# rectifiers.net
KiCad netlist of a schematic drawn in Altium Designer
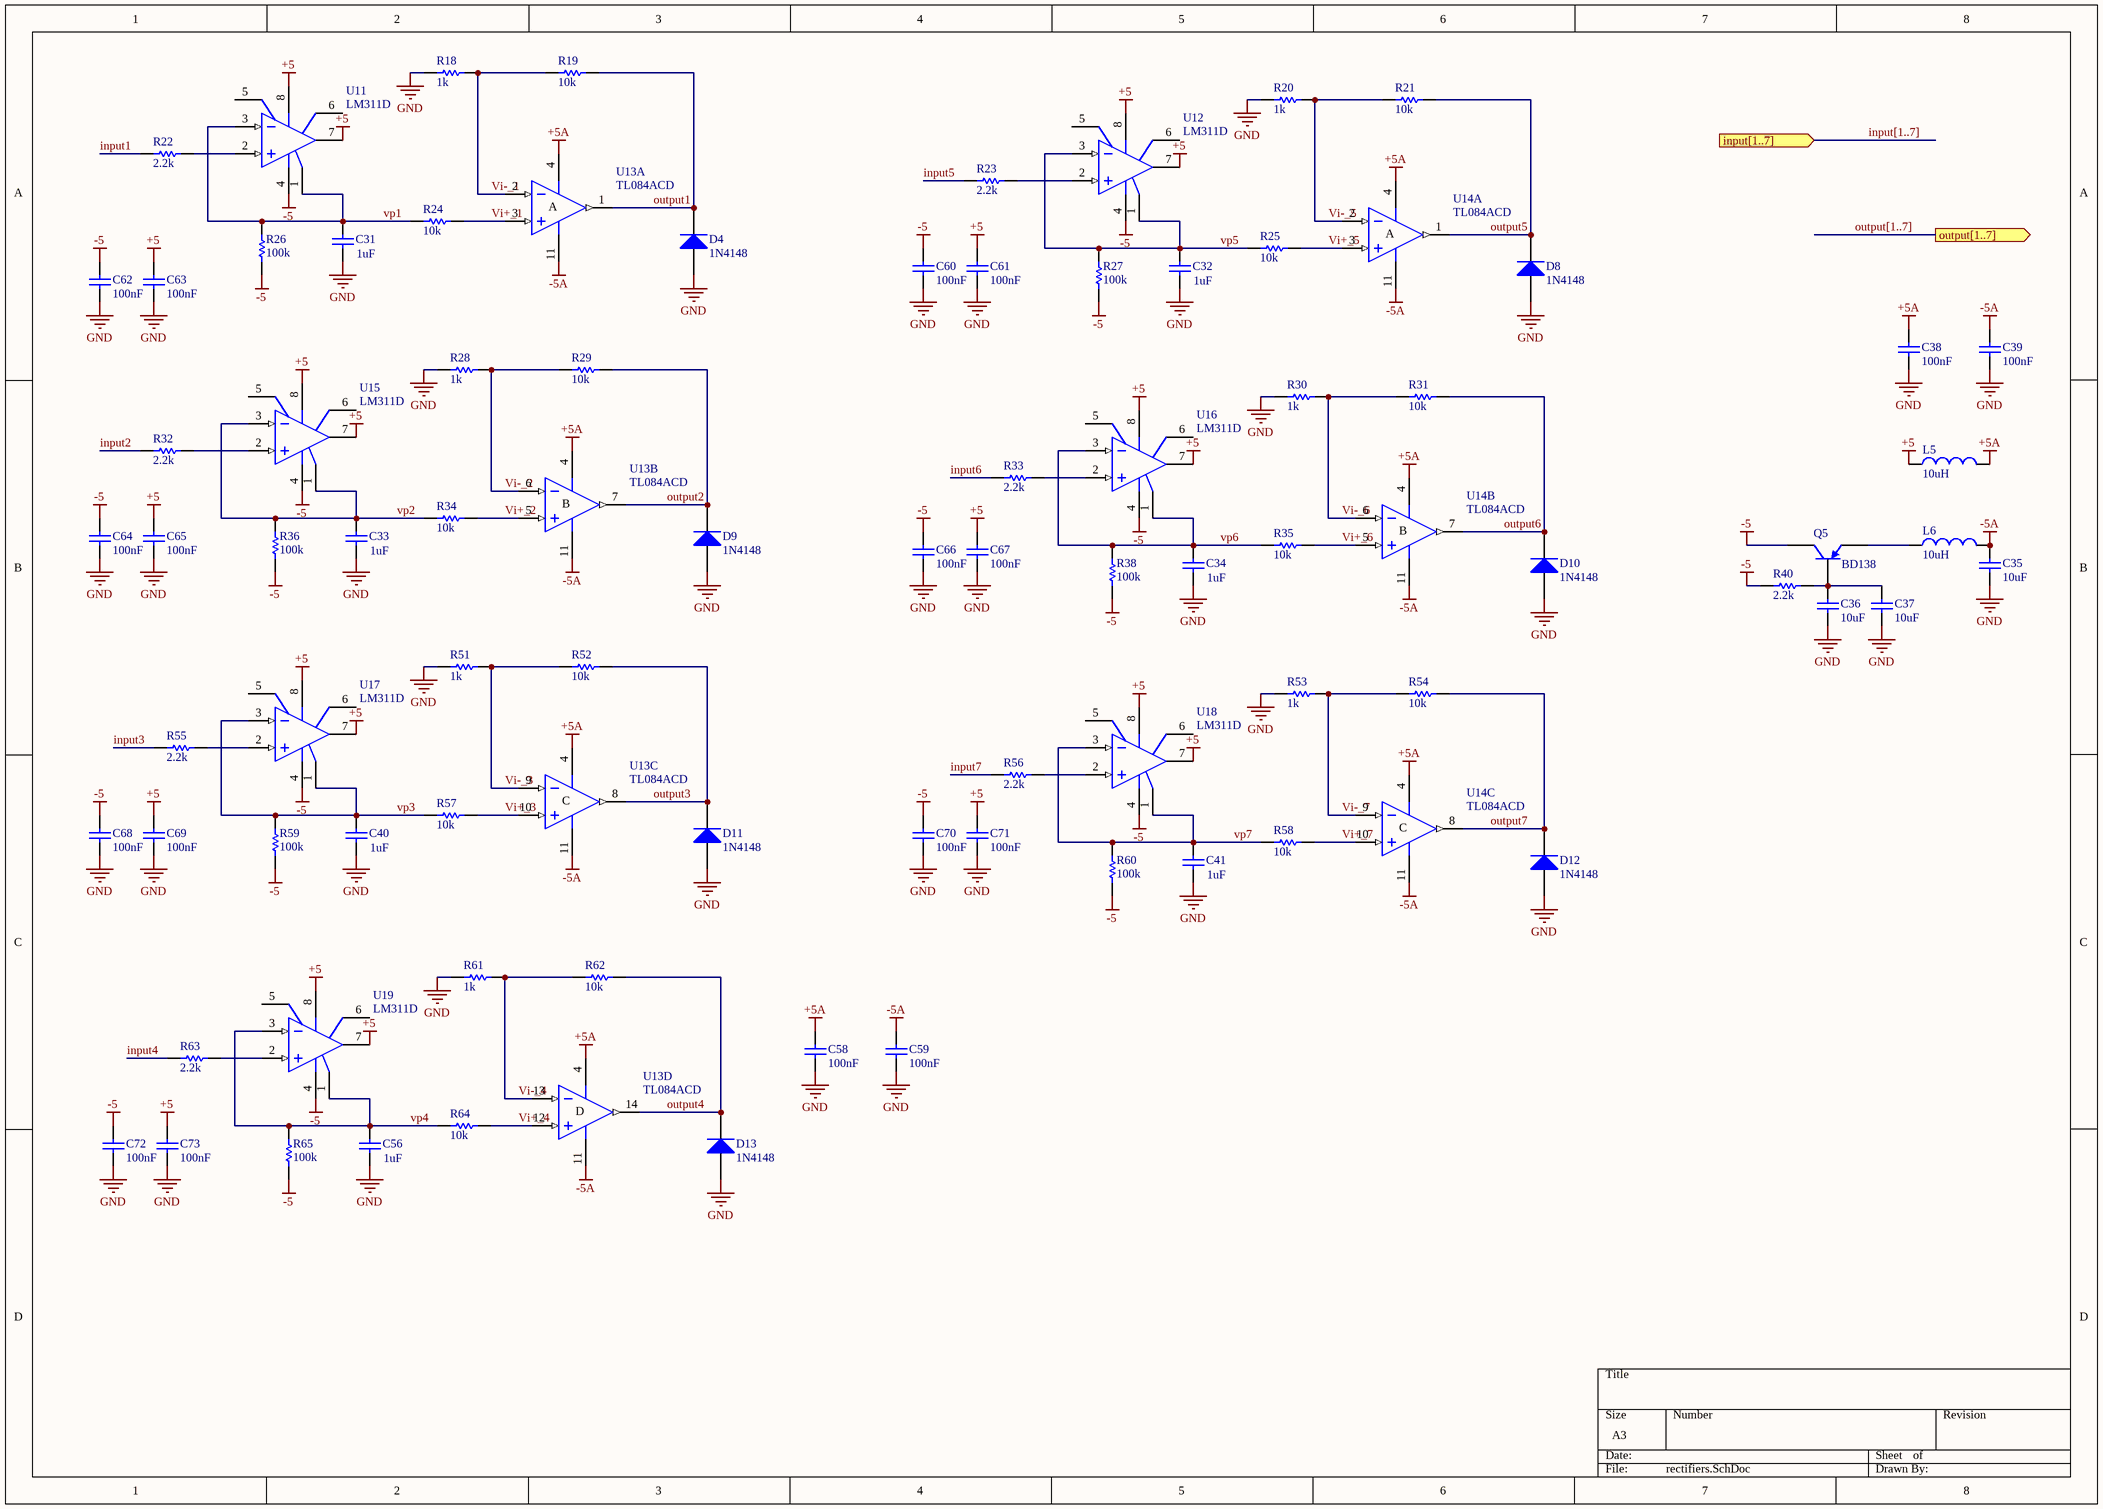
[diagram p0: rectifiers.SchDoc]

(export (version "E")
  (design (tool "Eeschema 10.0.6"))
  (components
    (comp (ref "C31")
      (value "1uF")
      (footprint "SMD_CAP_0805")
      (description "CAP-100Nf")
      (libsource (lib "Altium library (www.AVRelec.com)") (part "Cap ceramic"))
    )
    (comp (ref "C32")
      (value "1uF")
      (footprint "SMD_CAP_0805")
      (description "CAP-100Nf")
      (libsource (lib "Altium library (www.AVRelec.com)") (part "Cap ceramic"))
    )
    (comp (ref "C33")
      (value "1uF")
      (footprint "SMD_CAP_0805")
      (description "CAP-100Nf")
      (libsource (lib "Altium library (www.AVRelec.com)") (part "Cap ceramic"))
    )
    (comp (ref "C34")
      (value "1uF")
      (footprint "SMD_CAP_0805")
      (description "CAP-100Nf")
      (libsource (lib "Altium library (www.AVRelec.com)") (part "Cap ceramic"))
    )
    (comp (ref "C35")
      (value "10uF")
      (footprint "SMD_CAP_0805")
      (description "CAP-100Nf")
      (libsource (lib "Altium library (www.AVRelec.com)") (part "Cap ceramic"))
    )
    (comp (ref "C36")
      (value "10uF")
      (footprint "SMD_CAP_0805")
      (description "CAP-100Nf")
      (libsource (lib "Altium library (www.AVRelec.com)") (part "Cap ceramic"))
    )
    (comp (ref "C37")
      (value "10uF")
      (footprint "SMD_CAP_0805")
      (description "CAP-100Nf")
      (libsource (lib "Altium library (www.AVRelec.com)") (part "Cap ceramic"))
    )
    (comp (ref "C38")
      (value "100nF")
      (footprint "SMD_CAP_0805")
      (description "CAP-100Nf")
      (libsource (lib "Altium library (www.AVRelec.com)") (part "Cap ceramic"))
    )
    (comp (ref "C39")
      (value "100nF")
      (footprint "SMD_CAP_0805")
      (description "CAP-100Nf")
      (libsource (lib "Altium library (www.AVRelec.com)") (part "Cap ceramic"))
    )
    (comp (ref "C40")
      (value "1uF")
      (footprint "SMD_CAP_0805")
      (description "CAP-100Nf")
      (libsource (lib "Altium library (www.AVRelec.com)") (part "Cap ceramic"))
    )
    (comp (ref "C41")
      (value "1uF")
      (footprint "SMD_CAP_0805")
      (description "CAP-100Nf")
      (libsource (lib "Altium library (www.AVRelec.com)") (part "Cap ceramic"))
    )
    (comp (ref "C56")
      (value "1uF")
      (footprint "SMD_CAP_0805")
      (description "CAP-100Nf")
      (libsource (lib "Altium library (www.AVRelec.com)") (part "Cap ceramic"))
    )
    (comp (ref "C58")
      (value "100nF")
      (footprint "SMD_CAP_0805")
      (description "CAP-100Nf")
      (libsource (lib "Altium library (www.AVRelec.com)") (part "Cap ceramic"))
    )
    (comp (ref "C59")
      (value "100nF")
      (footprint "SMD_CAP_0805")
      (description "CAP-100Nf")
      (libsource (lib "Altium library (www.AVRelec.com)") (part "Cap ceramic"))
    )
    (comp (ref "C60")
      (value "100nF")
      (footprint "SMD_CAP_0805")
      (description "CAP-100Nf")
      (libsource (lib "Altium library (www.AVRelec.com)") (part "Cap ceramic"))
    )
    (comp (ref "C61")
      (value "100nF")
      (footprint "SMD_CAP_0805")
      (description "CAP-100Nf")
      (libsource (lib "Altium library (www.AVRelec.com)") (part "Cap ceramic"))
    )
    (comp (ref "C62")
      (value "100nF")
      (footprint "SMD_CAP_0805")
      (description "CAP-100Nf")
      (libsource (lib "Altium library (www.AVRelec.com)") (part "Cap ceramic"))
    )
    (comp (ref "C63")
      (value "100nF")
      (footprint "SMD_CAP_0805")
      (description "CAP-100Nf")
      (libsource (lib "Altium library (www.AVRelec.com)") (part "Cap ceramic"))
    )
    (comp (ref "C64")
      (value "100nF")
      (footprint "SMD_CAP_0805")
      (description "CAP-100Nf")
      (libsource (lib "Altium library (www.AVRelec.com)") (part "Cap ceramic"))
    )
    (comp (ref "C65")
      (value "100nF")
      (footprint "SMD_CAP_0805")
      (description "CAP-100Nf")
      (libsource (lib "Altium library (www.AVRelec.com)") (part "Cap ceramic"))
    )
    (comp (ref "C66")
      (value "100nF")
      (footprint "SMD_CAP_0805")
      (description "CAP-100Nf")
      (libsource (lib "Altium library (www.AVRelec.com)") (part "Cap ceramic"))
    )
    (comp (ref "C67")
      (value "100nF")
      (footprint "SMD_CAP_0805")
      (description "CAP-100Nf")
      (libsource (lib "Altium library (www.AVRelec.com)") (part "Cap ceramic"))
    )
    (comp (ref "C68")
      (value "100nF")
      (footprint "SMD_CAP_0805")
      (description "CAP-100Nf")
      (libsource (lib "Altium library (www.AVRelec.com)") (part "Cap ceramic"))
    )
    (comp (ref "C69")
      (value "100nF")
      (footprint "SMD_CAP_0805")
      (description "CAP-100Nf")
      (libsource (lib "Altium library (www.AVRelec.com)") (part "Cap ceramic"))
    )
    (comp (ref "C70")
      (value "100nF")
      (footprint "SMD_CAP_0805")
      (description "CAP-100Nf")
      (libsource (lib "Altium library (www.AVRelec.com)") (part "Cap ceramic"))
    )
    (comp (ref "C71")
      (value "100nF")
      (footprint "SMD_CAP_0805")
      (description "CAP-100Nf")
      (libsource (lib "Altium library (www.AVRelec.com)") (part "Cap ceramic"))
    )
    (comp (ref "C72")
      (value "100nF")
      (footprint "SMD_CAP_0805")
      (description "CAP-100Nf")
      (libsource (lib "Altium library (www.AVRelec.com)") (part "Cap ceramic"))
    )
    (comp (ref "C73")
      (value "100nF")
      (footprint "SMD_CAP_0805")
      (description "CAP-100Nf")
      (libsource (lib "Altium library (www.AVRelec.com)") (part "Cap ceramic"))
    )
    (comp (ref "D4")
      (value "1N4148")
      (footprint "LL4148")
      (description "High Conductance Fast Diode")
      (fields (field (name "PUBLISHER") "Altium Limited"))
      (libsource (lib "Miscellaneous Devices") (part "Diode 1N4148"))
    )
    (comp (ref "D8")
      (value "1N4148")
      (footprint "LL4148")
      (description "High Conductance Fast Diode")
      (fields (field (name "PUBLISHER") "Altium Limited"))
      (libsource (lib "Miscellaneous Devices") (part "Diode 1N4148"))
    )
    (comp (ref "D9")
      (value "1N4148")
      (footprint "LL4148")
      (description "High Conductance Fast Diode")
      (fields (field (name "PUBLISHER") "Altium Limited"))
      (libsource (lib "Miscellaneous Devices") (part "Diode 1N4148"))
    )
    (comp (ref "D10")
      (value "1N4148")
      (footprint "LL4148")
      (description "High Conductance Fast Diode")
      (fields (field (name "PUBLISHER") "Altium Limited"))
      (libsource (lib "Miscellaneous Devices") (part "Diode 1N4148"))
    )
    (comp (ref "D11")
      (value "1N4148")
      (footprint "LL4148")
      (description "High Conductance Fast Diode")
      (fields (field (name "PUBLISHER") "Altium Limited"))
      (libsource (lib "Miscellaneous Devices") (part "Diode 1N4148"))
    )
    (comp (ref "D12")
      (value "1N4148")
      (footprint "LL4148")
      (description "High Conductance Fast Diode")
      (fields (field (name "PUBLISHER") "Altium Limited"))
      (libsource (lib "Miscellaneous Devices") (part "Diode 1N4148"))
    )
    (comp (ref "D13")
      (value "1N4148")
      (footprint "LL4148")
      (description "High Conductance Fast Diode")
      (fields (field (name "PUBLISHER") "Altium Limited"))
      (libsource (lib "Miscellaneous Devices") (part "Diode 1N4148"))
    )
    (comp (ref "L5")
      (value "10uH")
      (footprint "IND1206")
      (description "Inductor")
      (fields (field (name "Comment") "inductor 10uH") (field (name "PUBLISHER") "Altium Limited"))
      (libsource (lib "Miscellaneous Devices") (part "Inductor"))
    )
    (comp (ref "L6")
      (value "10uH")
      (footprint "IND1206")
      (description "Inductor")
      (fields (field (name "Comment") "inductor 10uH") (field (name "PUBLISHER") "Altium Limited"))
      (libsource (lib "Miscellaneous Devices") (part "Inductor"))
    )
    (comp (ref "Q5")
      (value "BD138")
      (footprint "SOT-32")
      (description "PNP Transistor")
      (fields (field (name "E-MAIL") "picpars@gmail.com"))
      (libsource (lib "PicPars.com_usefully_Library") (part "BD138"))
    )
    (comp (ref "R18")
      (value "1k")
      (footprint "RES 0805 (2012X06L)")
      (description "Resistor")
      (fields (field (name "PUBLISHER") "Altium Limited"))
      (libsource (lib "Miscellaneous Devices") (part "Res1"))
    )
    (comp (ref "R19")
      (value "10k")
      (footprint "RES 0805 (2012X06L)")
      (description "Resistor")
      (fields (field (name "PUBLISHER") "Altium Limited"))
      (libsource (lib "Miscellaneous Devices") (part "Res1"))
    )
    (comp (ref "R20")
      (value "1k")
      (footprint "RES 0805 (2012X06L)")
      (description "Resistor")
      (fields (field (name "PUBLISHER") "Altium Limited"))
      (libsource (lib "Miscellaneous Devices") (part "Res1"))
    )
    (comp (ref "R21")
      (value "10k")
      (footprint "RES 0805 (2012X06L)")
      (description "Resistor")
      (fields (field (name "PUBLISHER") "Altium Limited"))
      (libsource (lib "Miscellaneous Devices") (part "Res1"))
    )
    (comp (ref "R22")
      (value "2.2k")
      (footprint "RES 0805 (2012X06L)")
      (description "Resistor")
      (fields (field (name "PUBLISHER") "Altium Limited"))
      (libsource (lib "Miscellaneous Devices") (part "Res1"))
    )
    (comp (ref "R23")
      (value "2.2k")
      (footprint "RES 0805 (2012X06L)")
      (description "Resistor")
      (fields (field (name "PUBLISHER") "Altium Limited"))
      (libsource (lib "Miscellaneous Devices") (part "Res1"))
    )
    (comp (ref "R24")
      (value "10k")
      (footprint "RES 0805 (2012X06L)")
      (description "Resistor")
      (fields (field (name "PUBLISHER") "Altium Limited"))
      (libsource (lib "Miscellaneous Devices") (part "Res1"))
    )
    (comp (ref "R25")
      (value "10k")
      (footprint "RES 0805 (2012X06L)")
      (description "Resistor")
      (fields (field (name "PUBLISHER") "Altium Limited"))
      (libsource (lib "Miscellaneous Devices") (part "Res1"))
    )
    (comp (ref "R26")
      (value "100k")
      (footprint "RES 0805 (2012X06L)")
      (description "Resistor")
      (fields (field (name "PUBLISHER") "Altium Limited"))
      (libsource (lib "Miscellaneous Devices") (part "Res1"))
    )
    (comp (ref "R27")
      (value "100k")
      (footprint "RES 0805 (2012X06L)")
      (description "Resistor")
      (fields (field (name "PUBLISHER") "Altium Limited"))
      (libsource (lib "Miscellaneous Devices") (part "Res1"))
    )
    (comp (ref "R28")
      (value "1k")
      (footprint "RES 0805 (2012X06L)")
      (description "Resistor")
      (fields (field (name "PUBLISHER") "Altium Limited"))
      (libsource (lib "Miscellaneous Devices") (part "Res1"))
    )
    (comp (ref "R29")
      (value "10k")
      (footprint "RES 0805 (2012X06L)")
      (description "Resistor")
      (fields (field (name "PUBLISHER") "Altium Limited"))
      (libsource (lib "Miscellaneous Devices") (part "Res1"))
    )
    (comp (ref "R30")
      (value "1k")
      (footprint "RES 0805 (2012X06L)")
      (description "Resistor")
      (fields (field (name "PUBLISHER") "Altium Limited"))
      (libsource (lib "Miscellaneous Devices") (part "Res1"))
    )
    (comp (ref "R31")
      (value "10k")
      (footprint "RES 0805 (2012X06L)")
      (description "Resistor")
      (fields (field (name "PUBLISHER") "Altium Limited"))
      (libsource (lib "Miscellaneous Devices") (part "Res1"))
    )
    (comp (ref "R32")
      (value "2.2k")
      (footprint "RES 0805 (2012X06L)")
      (description "Resistor")
      (fields (field (name "PUBLISHER") "Altium Limited"))
      (libsource (lib "Miscellaneous Devices") (part "Res1"))
    )
    (comp (ref "R33")
      (value "2.2k")
      (footprint "RES 0805 (2012X06L)")
      (description "Resistor")
      (fields (field (name "PUBLISHER") "Altium Limited"))
      (libsource (lib "Miscellaneous Devices") (part "Res1"))
    )
    (comp (ref "R34")
      (value "10k")
      (footprint "RES 0805 (2012X06L)")
      (description "Resistor")
      (fields (field (name "PUBLISHER") "Altium Limited"))
      (libsource (lib "Miscellaneous Devices") (part "Res1"))
    )
    (comp (ref "R35")
      (value "10k")
      (footprint "RES 0805 (2012X06L)")
      (description "Resistor")
      (fields (field (name "PUBLISHER") "Altium Limited"))
      (libsource (lib "Miscellaneous Devices") (part "Res1"))
    )
    (comp (ref "R36")
      (value "100k")
      (footprint "RES 0805 (2012X06L)")
      (description "Resistor")
      (fields (field (name "PUBLISHER") "Altium Limited"))
      (libsource (lib "Miscellaneous Devices") (part "Res1"))
    )
    (comp (ref "R38")
      (value "100k")
      (footprint "RES 0805 (2012X06L)")
      (description "Resistor")
      (fields (field (name "PUBLISHER") "Altium Limited"))
      (libsource (lib "Miscellaneous Devices") (part "Res1"))
    )
    (comp (ref "R40")
      (value "2.2k")
      (footprint "RES 0805 (2012X06L)")
      (description "Resistor")
      (fields (field (name "PUBLISHER") "Altium Limited"))
      (libsource (lib "Miscellaneous Devices") (part "Res1"))
    )
    (comp (ref "R51")
      (value "1k")
      (footprint "RES 0805 (2012X06L)")
      (description "Resistor")
      (fields (field (name "PUBLISHER") "Altium Limited"))
      (libsource (lib "Miscellaneous Devices") (part "Res1"))
    )
    (comp (ref "R52")
      (value "10k")
      (footprint "RES 0805 (2012X06L)")
      (description "Resistor")
      (fields (field (name "PUBLISHER") "Altium Limited"))
      (libsource (lib "Miscellaneous Devices") (part "Res1"))
    )
    (comp (ref "R53")
      (value "1k")
      (footprint "RES 0805 (2012X06L)")
      (description "Resistor")
      (fields (field (name "PUBLISHER") "Altium Limited"))
      (libsource (lib "Miscellaneous Devices") (part "Res1"))
    )
    (comp (ref "R54")
      (value "10k")
      (footprint "RES 0805 (2012X06L)")
      (description "Resistor")
      (fields (field (name "PUBLISHER") "Altium Limited"))
      (libsource (lib "Miscellaneous Devices") (part "Res1"))
    )
    (comp (ref "R55")
      (value "2.2k")
      (footprint "RES 0805 (2012X06L)")
      (description "Resistor")
      (fields (field (name "PUBLISHER") "Altium Limited"))
      (libsource (lib "Miscellaneous Devices") (part "Res1"))
    )
    (comp (ref "R56")
      (value "2.2k")
      (footprint "RES 0805 (2012X06L)")
      (description "Resistor")
      (fields (field (name "PUBLISHER") "Altium Limited"))
      (libsource (lib "Miscellaneous Devices") (part "Res1"))
    )
    (comp (ref "R57")
      (value "10k")
      (footprint "RES 0805 (2012X06L)")
      (description "Resistor")
      (fields (field (name "PUBLISHER") "Altium Limited"))
      (libsource (lib "Miscellaneous Devices") (part "Res1"))
    )
    (comp (ref "R58")
      (value "10k")
      (footprint "RES 0805 (2012X06L)")
      (description "Resistor")
      (fields (field (name "PUBLISHER") "Altium Limited"))
      (libsource (lib "Miscellaneous Devices") (part "Res1"))
    )
    (comp (ref "R59")
      (value "100k")
      (footprint "RES 0805 (2012X06L)")
      (description "Resistor")
      (fields (field (name "PUBLISHER") "Altium Limited"))
      (libsource (lib "Miscellaneous Devices") (part "Res1"))
    )
    (comp (ref "R60")
      (value "100k")
      (footprint "RES 0805 (2012X06L)")
      (description "Resistor")
      (fields (field (name "PUBLISHER") "Altium Limited"))
      (libsource (lib "Miscellaneous Devices") (part "Res1"))
    )
    (comp (ref "R61")
      (value "1k")
      (footprint "RES 0805 (2012X06L)")
      (description "Resistor")
      (fields (field (name "PUBLISHER") "Altium Limited"))
      (libsource (lib "Miscellaneous Devices") (part "Res1"))
    )
    (comp (ref "R62")
      (value "10k")
      (footprint "RES 0805 (2012X06L)")
      (description "Resistor")
      (fields (field (name "PUBLISHER") "Altium Limited"))
      (libsource (lib "Miscellaneous Devices") (part "Res1"))
    )
    (comp (ref "R63")
      (value "2.2k")
      (footprint "RES 0805 (2012X06L)")
      (description "Resistor")
      (fields (field (name "PUBLISHER") "Altium Limited"))
      (libsource (lib "Miscellaneous Devices") (part "Res1"))
    )
    (comp (ref "R64")
      (value "10k")
      (footprint "RES 0805 (2012X06L)")
      (description "Resistor")
      (fields (field (name "PUBLISHER") "Altium Limited"))
      (libsource (lib "Miscellaneous Devices") (part "Res1"))
    )
    (comp (ref "R65")
      (value "100k")
      (footprint "RES 0805 (2012X06L)")
      (description "Resistor")
      (fields (field (name "PUBLISHER") "Altium Limited"))
      (libsource (lib "Miscellaneous Devices") (part "Res1"))
    )
    (comp (ref "U11")
      (value "LM311D")
      (footprint "SO8_N")
      (description "Voltage Comparator")
      (fields (field (name "PUBLISHER") "Altium Limited"))
      (libsource (lib "ST Analog Comparator") (part "LM311D"))
    )
    (comp (ref "U12")
      (value "LM311D")
      (footprint "SO8_N")
      (description "Voltage Comparator")
      (fields (field (name "PUBLISHER") "Altium Limited"))
      (libsource (lib "ST Analog Comparator") (part "LM311D"))
    )
    (comp (ref "U13")
      (value "TL084ACD")
      (footprint "SO14_N")
      (description "General-Purpose J-FET Quad Operational Amplifier")
      (fields (field (name "PUBLISHER") "Altium Limited"))
      (libsource (lib "ST Operational Amplifier") (part "TL084ACD"))
    )
    (comp (ref "U14")
      (value "TL084ACD")
      (footprint "SO14_N")
      (description "General-Purpose J-FET Quad Operational Amplifier")
      (fields (field (name "PUBLISHER") "Altium Limited"))
      (libsource (lib "ST Operational Amplifier") (part "TL084ACD"))
    )
    (comp (ref "U15")
      (value "LM311D")
      (footprint "SO8_N")
      (description "Voltage Comparator")
      (fields (field (name "PUBLISHER") "Altium Limited"))
      (libsource (lib "ST Analog Comparator") (part "LM311D"))
    )
    (comp (ref "U16")
      (value "LM311D")
      (footprint "SO8_N")
      (description "Voltage Comparator")
      (fields (field (name "PUBLISHER") "Altium Limited"))
      (libsource (lib "ST Analog Comparator") (part "LM311D"))
    )
    (comp (ref "U17")
      (value "LM311D")
      (footprint "SO8_N")
      (description "Voltage Comparator")
      (fields (field (name "PUBLISHER") "Altium Limited"))
      (libsource (lib "ST Analog Comparator") (part "LM311D"))
    )
    (comp (ref "U18")
      (value "LM311D")
      (footprint "SO8_N")
      (description "Voltage Comparator")
      (fields (field (name "PUBLISHER") "Altium Limited"))
      (libsource (lib "ST Analog Comparator") (part "LM311D"))
    )
    (comp (ref "U19")
      (value "LM311D")
      (footprint "SO8_N")
      (description "Voltage Comparator")
      (fields (field (name "PUBLISHER") "Altium Limited"))
      (libsource (lib "ST Analog Comparator") (part "LM311D"))
    )
  )
  (nets
    (net (code "1") (name "+5") (class "Default")
      (node (ref "C61") (pin "2") (pinfunction "2_2") (pintype "passive"))
      (node (ref "C63") (pin "2") (pinfunction "2_2") (pintype "passive"))
      (node (ref "C65") (pin "2") (pinfunction "2_2") (pintype "passive"))
      (node (ref "C67") (pin "2") (pinfunction "2_2") (pintype "passive"))
      (node (ref "C69") (pin "2") (pinfunction "2_2") (pintype "passive"))
      (node (ref "C71") (pin "2") (pinfunction "2_2") (pintype "passive"))
      (node (ref "C73") (pin "2") (pinfunction "2_2") (pintype "passive"))
      (node (ref "L5") (pin "1") (pinfunction "1_1") (pintype "passive"))
      (node (ref "U11") (pin "7") (pinfunction "OUT_7") (pintype "open_collector"))
      (node (ref "U11") (pin "8") (pinfunction "V+_8") (pintype "power_in"))
      (node (ref "U12") (pin "7") (pinfunction "OUT_7") (pintype "open_collector"))
      (node (ref "U12") (pin "8") (pinfunction "V+_8") (pintype "power_in"))
      (node (ref "U15") (pin "7") (pinfunction "OUT_7") (pintype "open_collector"))
      (node (ref "U15") (pin "8") (pinfunction "V+_8") (pintype "power_in"))
      (node (ref "U16") (pin "7") (pinfunction "OUT_7") (pintype "open_collector"))
      (node (ref "U16") (pin "8") (pinfunction "V+_8") (pintype "power_in"))
      (node (ref "U17") (pin "7") (pinfunction "OUT_7") (pintype "open_collector"))
      (node (ref "U17") (pin "8") (pinfunction "V+_8") (pintype "power_in"))
      (node (ref "U18") (pin "7") (pinfunction "OUT_7") (pintype "open_collector"))
      (node (ref "U18") (pin "8") (pinfunction "V+_8") (pintype "power_in"))
      (node (ref "U19") (pin "7") (pinfunction "OUT_7") (pintype "open_collector"))
      (node (ref "U19") (pin "8") (pinfunction "V+_8") (pintype "power_in"))
    )
    (net (code "2") (name "+5A") (class "Default")
      (node (ref "C38") (pin "2") (pinfunction "2_2") (pintype "passive"))
      (node (ref "C58") (pin "2") (pinfunction "2_2") (pintype "passive"))
      (node (ref "L5") (pin "2") (pinfunction "2_2") (pintype "passive"))
      (node (ref "U13") (pin "4") (pinfunction "V+_4") (pintype "power_in"))
      (node (ref "U14") (pin "4") (pinfunction "V+_4") (pintype "power_in"))
    )
    (net (code "3") (name "-5") (class "Default")
      (node (ref "C60") (pin "2") (pinfunction "2_2") (pintype "passive"))
      (node (ref "C62") (pin "2") (pinfunction "2_2") (pintype "passive"))
      (node (ref "C64") (pin "2") (pinfunction "2_2") (pintype "passive"))
      (node (ref "C66") (pin "2") (pinfunction "2_2") (pintype "passive"))
      (node (ref "C68") (pin "2") (pinfunction "2_2") (pintype "passive"))
      (node (ref "C70") (pin "2") (pinfunction "2_2") (pintype "passive"))
      (node (ref "C72") (pin "2") (pinfunction "2_2") (pintype "passive"))
      (node (ref "Q5") (pin "C") (pinfunction "C_C") (pintype "passive"))
      (node (ref "R26") (pin "2") (pinfunction "2_2") (pintype "passive"))
      (node (ref "R27") (pin "2") (pinfunction "2_2") (pintype "passive"))
      (node (ref "R36") (pin "2") (pinfunction "2_2") (pintype "passive"))
      (node (ref "R38") (pin "2") (pinfunction "2_2") (pintype "passive"))
      (node (ref "R40") (pin "2") (pinfunction "2_2") (pintype "passive"))
      (node (ref "R59") (pin "2") (pinfunction "2_2") (pintype "passive"))
      (node (ref "R60") (pin "2") (pinfunction "2_2") (pintype "passive"))
      (node (ref "R65") (pin "2") (pinfunction "2_2") (pintype "passive"))
      (node (ref "U11") (pin "4") (pinfunction "V-_(CASE)_4") (pintype "power_in"))
      (node (ref "U12") (pin "4") (pinfunction "V-_(CASE)_4") (pintype "power_in"))
      (node (ref "U15") (pin "4") (pinfunction "V-_(CASE)_4") (pintype "power_in"))
      (node (ref "U16") (pin "4") (pinfunction "V-_(CASE)_4") (pintype "power_in"))
      (node (ref "U17") (pin "4") (pinfunction "V-_(CASE)_4") (pintype "power_in"))
      (node (ref "U18") (pin "4") (pinfunction "V-_(CASE)_4") (pintype "power_in"))
      (node (ref "U19") (pin "4") (pinfunction "V-_(CASE)_4") (pintype "power_in"))
    )
    (net (code "4") (name "-5A") (class "Default")
      (node (ref "C35") (pin "2") (pinfunction "2_2") (pintype "passive"))
      (node (ref "C39") (pin "2") (pinfunction "2_2") (pintype "passive"))
      (node (ref "C59") (pin "2") (pinfunction "2_2") (pintype "passive"))
      (node (ref "L6") (pin "2") (pinfunction "2_2") (pintype "passive"))
      (node (ref "U13") (pin "11") (pinfunction "V-_11") (pintype "power_in"))
      (node (ref "U14") (pin "11") (pinfunction "V-_11") (pintype "power_in"))
    )
    (net (code "5") (name "/Vi+_1") (class "Default")
      (node (ref "R24") (pin "1") (pinfunction "1_1") (pintype "passive"))
      (node (ref "U13") (pin "3") (pinfunction "IN+_3") (pintype "input"))
    )
    (net (code "6") (name "/Vi+_2") (class "Default")
      (node (ref "R34") (pin "1") (pinfunction "1_1") (pintype "passive"))
      (node (ref "U13") (pin "5") (pinfunction "IN+_5") (pintype "input"))
    )
    (net (code "7") (name "/Vi+_3") (class "Default")
      (node (ref "R57") (pin "1") (pinfunction "1_1") (pintype "passive"))
      (node (ref "U13") (pin "10") (pinfunction "IN+_10") (pintype "input"))
    )
    (net (code "8") (name "/Vi+_4") (class "Default")
      (node (ref "R64") (pin "1") (pinfunction "1_1") (pintype "passive"))
      (node (ref "U13") (pin "12") (pinfunction "IN+_12") (pintype "input"))
    )
    (net (code "9") (name "/Vi+_5") (class "Default")
      (node (ref "R25") (pin "1") (pinfunction "1_1") (pintype "passive"))
      (node (ref "U14") (pin "3") (pinfunction "IN+_3") (pintype "input"))
    )
    (net (code "10") (name "/Vi+_6") (class "Default")
      (node (ref "R35") (pin "1") (pinfunction "1_1") (pintype "passive"))
      (node (ref "U14") (pin "5") (pinfunction "IN+_5") (pintype "input"))
    )
    (net (code "11") (name "/Vi+_7") (class "Default")
      (node (ref "R58") (pin "1") (pinfunction "1_1") (pintype "passive"))
      (node (ref "U14") (pin "10") (pinfunction "IN+_10") (pintype "input"))
    )
    (net (code "12") (name "/Vi-_1") (class "Default")
      (node (ref "R18") (pin "1") (pinfunction "1_1") (pintype "passive"))
      (node (ref "R19") (pin "2") (pinfunction "2_2") (pintype "passive"))
      (node (ref "U13") (pin "2") (pinfunction "IN-_2") (pintype "input"))
    )
    (net (code "13") (name "/Vi-_2") (class "Default")
      (node (ref "R28") (pin "1") (pinfunction "1_1") (pintype "passive"))
      (node (ref "R29") (pin "2") (pinfunction "2_2") (pintype "passive"))
      (node (ref "U13") (pin "6") (pinfunction "IN-_6") (pintype "input"))
    )
    (net (code "14") (name "/Vi-_3") (class "Default")
      (node (ref "R51") (pin "1") (pinfunction "1_1") (pintype "passive"))
      (node (ref "R52") (pin "2") (pinfunction "2_2") (pintype "passive"))
      (node (ref "U13") (pin "9") (pinfunction "IN-_9") (pintype "input"))
    )
    (net (code "15") (name "/Vi-_4") (class "Default")
      (node (ref "R61") (pin "1") (pinfunction "1_1") (pintype "passive"))
      (node (ref "R62") (pin "2") (pinfunction "2_2") (pintype "passive"))
      (node (ref "U13") (pin "13") (pinfunction "IN-_13") (pintype "input"))
    )
    (net (code "16") (name "/Vi-_5") (class "Default")
      (node (ref "R20") (pin "1") (pinfunction "1_1") (pintype "passive"))
      (node (ref "R21") (pin "2") (pinfunction "2_2") (pintype "passive"))
      (node (ref "U14") (pin "2") (pinfunction "IN-_2") (pintype "input"))
    )
    (net (code "17") (name "/Vi-_6") (class "Default")
      (node (ref "R30") (pin "1") (pinfunction "1_1") (pintype "passive"))
      (node (ref "R31") (pin "2") (pinfunction "2_2") (pintype "passive"))
      (node (ref "U14") (pin "6") (pinfunction "IN-_6") (pintype "input"))
    )
    (net (code "18") (name "/Vi-_7") (class "Default")
      (node (ref "R53") (pin "1") (pinfunction "1_1") (pintype "passive"))
      (node (ref "R54") (pin "2") (pinfunction "2_2") (pintype "passive"))
      (node (ref "U14") (pin "9") (pinfunction "IN-_9") (pintype "input"))
    )
    (net (code "19") (name "/input1") (class "Default")
      (node (ref "R22") (pin "2") (pinfunction "2_2") (pintype "passive"))
    )
    (net (code "20") (name "/input2") (class "Default")
      (node (ref "R32") (pin "2") (pinfunction "2_2") (pintype "passive"))
    )
    (net (code "21") (name "/input3") (class "Default")
      (node (ref "R55") (pin "2") (pinfunction "2_2") (pintype "passive"))
    )
    (net (code "22") (name "/input4") (class "Default")
      (node (ref "R63") (pin "2") (pinfunction "2_2") (pintype "passive"))
    )
    (net (code "23") (name "/input5") (class "Default")
      (node (ref "R23") (pin "2") (pinfunction "2_2") (pintype "passive"))
    )
    (net (code "24") (name "/input6") (class "Default")
      (node (ref "R33") (pin "2") (pinfunction "2_2") (pintype "passive"))
    )
    (net (code "25") (name "/input7") (class "Default")
      (node (ref "R56") (pin "2") (pinfunction "2_2") (pintype "passive"))
    )
    (net (code "27") (name "/output1") (class "Default")
      (node (ref "D4") (pin "2") (pinfunction "K_2") (pintype "passive"))
      (node (ref "R19") (pin "1") (pinfunction "1_1") (pintype "passive"))
      (node (ref "U13") (pin "1") (pinfunction "OUT_1") (pintype "output"))
    )
    (net (code "28") (name "/output2") (class "Default")
      (node (ref "D9") (pin "2") (pinfunction "K_2") (pintype "passive"))
      (node (ref "R29") (pin "1") (pinfunction "1_1") (pintype "passive"))
      (node (ref "U13") (pin "7") (pinfunction "OUT_7") (pintype "output"))
    )
    (net (code "29") (name "/output3") (class "Default")
      (node (ref "D11") (pin "2") (pinfunction "K_2") (pintype "passive"))
      (node (ref "R52") (pin "1") (pinfunction "1_1") (pintype "passive"))
      (node (ref "U13") (pin "8") (pinfunction "OUT_8") (pintype "output"))
    )
    (net (code "30") (name "/output4") (class "Default")
      (node (ref "D13") (pin "2") (pinfunction "K_2") (pintype "passive"))
      (node (ref "R62") (pin "1") (pinfunction "1_1") (pintype "passive"))
      (node (ref "U13") (pin "14") (pinfunction "OUT_14") (pintype "output"))
    )
    (net (code "31") (name "/output5") (class "Default")
      (node (ref "D8") (pin "2") (pinfunction "K_2") (pintype "passive"))
      (node (ref "R21") (pin "1") (pinfunction "1_1") (pintype "passive"))
      (node (ref "U14") (pin "1") (pinfunction "OUT_1") (pintype "output"))
    )
    (net (code "32") (name "/output6") (class "Default")
      (node (ref "D10") (pin "2") (pinfunction "K_2") (pintype "passive"))
      (node (ref "R31") (pin "1") (pinfunction "1_1") (pintype "passive"))
      (node (ref "U14") (pin "7") (pinfunction "OUT_7") (pintype "output"))
    )
    (net (code "33") (name "/output7") (class "Default")
      (node (ref "D12") (pin "2") (pinfunction "K_2") (pintype "passive"))
      (node (ref "R54") (pin "1") (pinfunction "1_1") (pintype "passive"))
      (node (ref "U14") (pin "8") (pinfunction "OUT_8") (pintype "output"))
    )
    (net (code "35") (name "/vp1") (class "Default")
      (node (ref "C31") (pin "2") (pinfunction "2_2") (pintype "passive"))
      (node (ref "R24") (pin "2") (pinfunction "2_2") (pintype "passive"))
      (node (ref "R26") (pin "1") (pinfunction "1_1") (pintype "passive"))
      (node (ref "U11") (pin "1") (pinfunction "GND_1") (pintype "power_in"))
      (node (ref "U11") (pin "3") (pinfunction "IN-_3") (pintype "input"))
    )
    (net (code "36") (name "/vp2") (class "Default")
      (node (ref "C33") (pin "2") (pinfunction "2_2") (pintype "passive"))
      (node (ref "R34") (pin "2") (pinfunction "2_2") (pintype "passive"))
      (node (ref "R36") (pin "1") (pinfunction "1_1") (pintype "passive"))
      (node (ref "U15") (pin "1") (pinfunction "GND_1") (pintype "power_in"))
      (node (ref "U15") (pin "3") (pinfunction "IN-_3") (pintype "input"))
    )
    (net (code "37") (name "/vp3") (class "Default")
      (node (ref "C40") (pin "2") (pinfunction "2_2") (pintype "passive"))
      (node (ref "R57") (pin "2") (pinfunction "2_2") (pintype "passive"))
      (node (ref "R59") (pin "1") (pinfunction "1_1") (pintype "passive"))
      (node (ref "U17") (pin "1") (pinfunction "GND_1") (pintype "power_in"))
      (node (ref "U17") (pin "3") (pinfunction "IN-_3") (pintype "input"))
    )
    (net (code "38") (name "/vp4") (class "Default")
      (node (ref "C56") (pin "2") (pinfunction "2_2") (pintype "passive"))
      (node (ref "R64") (pin "2") (pinfunction "2_2") (pintype "passive"))
      (node (ref "R65") (pin "1") (pinfunction "1_1") (pintype "passive"))
      (node (ref "U19") (pin "1") (pinfunction "GND_1") (pintype "power_in"))
      (node (ref "U19") (pin "3") (pinfunction "IN-_3") (pintype "input"))
    )
    (net (code "39") (name "/vp5") (class "Default")
      (node (ref "C32") (pin "2") (pinfunction "2_2") (pintype "passive"))
      (node (ref "R25") (pin "2") (pinfunction "2_2") (pintype "passive"))
      (node (ref "R27") (pin "1") (pinfunction "1_1") (pintype "passive"))
      (node (ref "U12") (pin "1") (pinfunction "GND_1") (pintype "power_in"))
      (node (ref "U12") (pin "3") (pinfunction "IN-_3") (pintype "input"))
    )
    (net (code "40") (name "/vp6") (class "Default")
      (node (ref "C34") (pin "2") (pinfunction "2_2") (pintype "passive"))
      (node (ref "R35") (pin "2") (pinfunction "2_2") (pintype "passive"))
      (node (ref "R38") (pin "1") (pinfunction "1_1") (pintype "passive"))
      (node (ref "U16") (pin "1") (pinfunction "GND_1") (pintype "power_in"))
      (node (ref "U16") (pin "3") (pinfunction "IN-_3") (pintype "input"))
    )
    (net (code "41") (name "/vp7") (class "Default")
      (node (ref "C41") (pin "2") (pinfunction "2_2") (pintype "passive"))
      (node (ref "R58") (pin "2") (pinfunction "2_2") (pintype "passive"))
      (node (ref "R60") (pin "1") (pinfunction "1_1") (pintype "passive"))
      (node (ref "U18") (pin "1") (pinfunction "GND_1") (pintype "power_in"))
      (node (ref "U18") (pin "3") (pinfunction "IN-_3") (pintype "input"))
    )
    (net (code "42") (name "GND") (class "Default")
      (node (ref "C31") (pin "1") (pinfunction "1_1") (pintype "passive"))
      (node (ref "C32") (pin "1") (pinfunction "1_1") (pintype "passive"))
      (node (ref "C33") (pin "1") (pinfunction "1_1") (pintype "passive"))
      (node (ref "C34") (pin "1") (pinfunction "1_1") (pintype "passive"))
      (node (ref "C35") (pin "1") (pinfunction "1_1") (pintype "passive"))
      (node (ref "C36") (pin "1") (pinfunction "1_1") (pintype "passive"))
      (node (ref "C37") (pin "1") (pinfunction "1_1") (pintype "passive"))
      (node (ref "C38") (pin "1") (pinfunction "1_1") (pintype "passive"))
      (node (ref "C39") (pin "1") (pinfunction "1_1") (pintype "passive"))
      (node (ref "C40") (pin "1") (pinfunction "1_1") (pintype "passive"))
      (node (ref "C41") (pin "1") (pinfunction "1_1") (pintype "passive"))
      (node (ref "C56") (pin "1") (pinfunction "1_1") (pintype "passive"))
      (node (ref "C58") (pin "1") (pinfunction "1_1") (pintype "passive"))
      (node (ref "C59") (pin "1") (pinfunction "1_1") (pintype "passive"))
      (node (ref "C60") (pin "1") (pinfunction "1_1") (pintype "passive"))
      (node (ref "C61") (pin "1") (pinfunction "1_1") (pintype "passive"))
      (node (ref "C62") (pin "1") (pinfunction "1_1") (pintype "passive"))
      (node (ref "C63") (pin "1") (pinfunction "1_1") (pintype "passive"))
      (node (ref "C64") (pin "1") (pinfunction "1_1") (pintype "passive"))
      (node (ref "C65") (pin "1") (pinfunction "1_1") (pintype "passive"))
      (node (ref "C66") (pin "1") (pinfunction "1_1") (pintype "passive"))
      (node (ref "C67") (pin "1") (pinfunction "1_1") (pintype "passive"))
      (node (ref "C68") (pin "1") (pinfunction "1_1") (pintype "passive"))
      (node (ref "C69") (pin "1") (pinfunction "1_1") (pintype "passive"))
      (node (ref "C70") (pin "1") (pinfunction "1_1") (pintype "passive"))
      (node (ref "C71") (pin "1") (pinfunction "1_1") (pintype "passive"))
      (node (ref "C72") (pin "1") (pinfunction "1_1") (pintype "passive"))
      (node (ref "C73") (pin "1") (pinfunction "1_1") (pintype "passive"))
      (node (ref "D10") (pin "1") (pinfunction "A_1") (pintype "passive"))
      (node (ref "D11") (pin "1") (pinfunction "A_1") (pintype "passive"))
      (node (ref "D12") (pin "1") (pinfunction "A_1") (pintype "passive"))
      (node (ref "D13") (pin "1") (pinfunction "A_1") (pintype "passive"))
      (node (ref "D4") (pin "1") (pinfunction "A_1") (pintype "passive"))
      (node (ref "D8") (pin "1") (pinfunction "A_1") (pintype "passive"))
      (node (ref "D9") (pin "1") (pinfunction "A_1") (pintype "passive"))
      (node (ref "R18") (pin "2") (pinfunction "2_2") (pintype "passive"))
      (node (ref "R20") (pin "2") (pinfunction "2_2") (pintype "passive"))
      (node (ref "R28") (pin "2") (pinfunction "2_2") (pintype "passive"))
      (node (ref "R30") (pin "2") (pinfunction "2_2") (pintype "passive"))
      (node (ref "R51") (pin "2") (pinfunction "2_2") (pintype "passive"))
      (node (ref "R53") (pin "2") (pinfunction "2_2") (pintype "passive"))
      (node (ref "R61") (pin "2") (pinfunction "2_2") (pintype "passive"))
    )
    (net (code "43") (name "Net-(C36-Pad2)") (class "Default")
      (node (ref "C36") (pin "2") (pinfunction "2_2") (pintype "passive"))
      (node (ref "C37") (pin "2") (pinfunction "2_2") (pintype "passive"))
      (node (ref "Q5") (pin "B") (pinfunction "B_B") (pintype "passive"))
      (node (ref "R40") (pin "1") (pinfunction "1_1") (pintype "passive"))
    )
    (net (code "44") (name "Net-(L6-Pad1)") (class "Default")
      (node (ref "L6") (pin "1") (pinfunction "1_1") (pintype "passive"))
      (node (ref "Q5") (pin "E") (pinfunction "E_E") (pintype "passive"))
    )
    (net (code "45") (name "Net-(U11-IN+)") (class "Default")
      (node (ref "R22") (pin "1") (pinfunction "1_1") (pintype "passive"))
      (node (ref "U11") (pin "2") (pinfunction "IN+_2") (pintype "input"))
    )
    (net (code "46") (name "Net-(U12-IN+)") (class "Default")
      (node (ref "R23") (pin "1") (pinfunction "1_1") (pintype "passive"))
      (node (ref "U12") (pin "2") (pinfunction "IN+_2") (pintype "input"))
    )
    (net (code "47") (name "Net-(U15-IN+)") (class "Default")
      (node (ref "R32") (pin "1") (pinfunction "1_1") (pintype "passive"))
      (node (ref "U15") (pin "2") (pinfunction "IN+_2") (pintype "input"))
    )
    (net (code "48") (name "Net-(U16-IN+)") (class "Default")
      (node (ref "R33") (pin "1") (pinfunction "1_1") (pintype "passive"))
      (node (ref "U16") (pin "2") (pinfunction "IN+_2") (pintype "input"))
    )
    (net (code "49") (name "Net-(U17-IN+)") (class "Default")
      (node (ref "R55") (pin "1") (pinfunction "1_1") (pintype "passive"))
      (node (ref "U17") (pin "2") (pinfunction "IN+_2") (pintype "input"))
    )
    (net (code "50") (name "Net-(U18-IN+)") (class "Default")
      (node (ref "R56") (pin "1") (pinfunction "1_1") (pintype "passive"))
      (node (ref "U18") (pin "2") (pinfunction "IN+_2") (pintype "input"))
    )
    (net (code "51") (name "Net-(U19-IN+)") (class "Default")
      (node (ref "R63") (pin "1") (pinfunction "1_1") (pintype "passive"))
      (node (ref "U19") (pin "2") (pinfunction "IN+_2") (pintype "input"))
    )
    (net (code "52") (name "unconnected-(U11-BAL-Pad5)") (class "Default")
      (node (ref "U11") (pin "5") (pinfunction "BAL_5") (pintype "passive"))
    )
    (net (code "53") (name "unconnected-(U11-BAL{slash}STB-Pad6)") (class "Default")
      (node (ref "U11") (pin "6") (pinfunction "BAL/STB_6") (pintype "passive"))
    )
    (net (code "54") (name "unconnected-(U12-BAL-Pad5)") (class "Default")
      (node (ref "U12") (pin "5") (pinfunction "BAL_5") (pintype "passive"))
    )
    (net (code "55") (name "unconnected-(U12-BAL{slash}STB-Pad6)") (class "Default")
      (node (ref "U12") (pin "6") (pinfunction "BAL/STB_6") (pintype "passive"))
    )
    (net (code "56") (name "unconnected-(U15-BAL-Pad5)") (class "Default")
      (node (ref "U15") (pin "5") (pinfunction "BAL_5") (pintype "passive"))
    )
    (net (code "57") (name "unconnected-(U15-BAL{slash}STB-Pad6)") (class "Default")
      (node (ref "U15") (pin "6") (pinfunction "BAL/STB_6") (pintype "passive"))
    )
    (net (code "58") (name "unconnected-(U16-BAL-Pad5)") (class "Default")
      (node (ref "U16") (pin "5") (pinfunction "BAL_5") (pintype "passive"))
    )
    (net (code "59") (name "unconnected-(U16-BAL{slash}STB-Pad6)") (class "Default")
      (node (ref "U16") (pin "6") (pinfunction "BAL/STB_6") (pintype "passive"))
    )
    (net (code "60") (name "unconnected-(U17-BAL-Pad5)") (class "Default")
      (node (ref "U17") (pin "5") (pinfunction "BAL_5") (pintype "passive"))
    )
    (net (code "61") (name "unconnected-(U17-BAL{slash}STB-Pad6)") (class "Default")
      (node (ref "U17") (pin "6") (pinfunction "BAL/STB_6") (pintype "passive"))
    )
    (net (code "62") (name "unconnected-(U18-BAL-Pad5)") (class "Default")
      (node (ref "U18") (pin "5") (pinfunction "BAL_5") (pintype "passive"))
    )
    (net (code "63") (name "unconnected-(U18-BAL{slash}STB-Pad6)") (class "Default")
      (node (ref "U18") (pin "6") (pinfunction "BAL/STB_6") (pintype "passive"))
    )
    (net (code "64") (name "unconnected-(U19-BAL-Pad5)") (class "Default")
      (node (ref "U19") (pin "5") (pinfunction "BAL_5") (pintype "passive"))
    )
    (net (code "65") (name "unconnected-(U19-BAL{slash}STB-Pad6)") (class "Default")
      (node (ref "U19") (pin "6") (pinfunction "BAL/STB_6") (pintype "passive"))
    )
  )
)
